# VM_Protection_Circuit.net
KiCad netlist of a schematic drawn in EAGLE
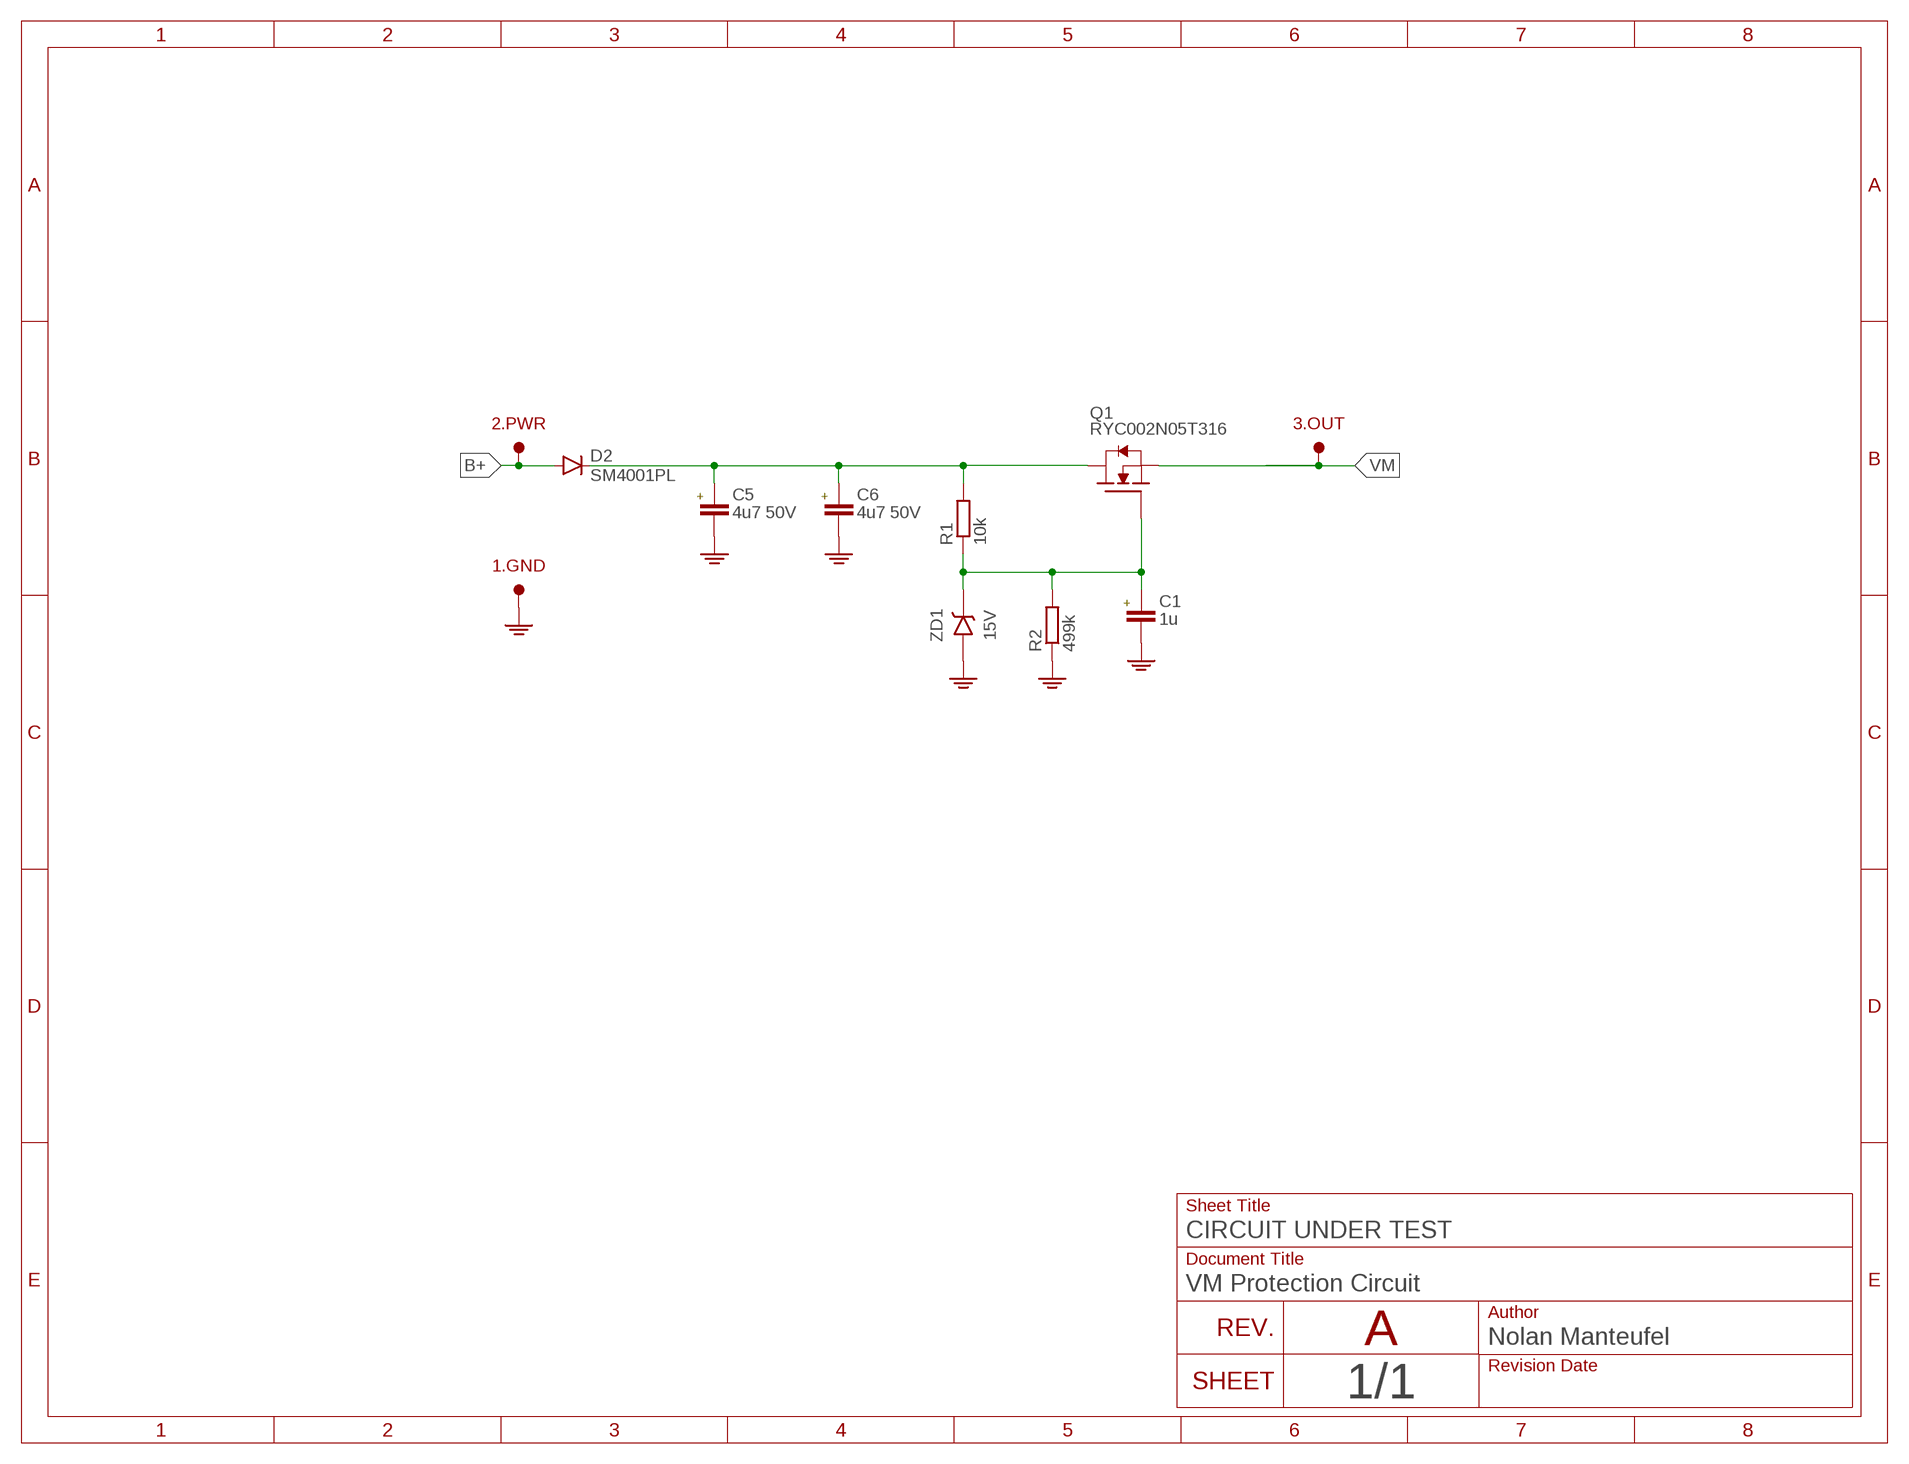
[diagram p0: schematic, sheet 1]

(export (version "E")
  (design (tool "Eeschema 10.0.6"))
  (components
    (comp (ref "1.GND")
      (value "TESTPOINTKE5000-SMTEXT")
      (footprint "eagle-import:PINS_1_TESTPOINT_KE5000_NOTEXT")
      (libsource (lib "eagle-import") (part "TESTPOINTKE5000-SMTEXT"))
    )
    (comp (ref "2.PWR")
      (value "TESTPOINTKE5000-SMTEXT")
      (footprint "eagle-import:PINS_1_TESTPOINT_KE5000_NOTEXT")
      (libsource (lib "eagle-import") (part "TESTPOINTKE5000-SMTEXT"))
    )
    (comp (ref "3.OUT")
      (value "TESTPOINTKE5000-SMTEXT")
      (footprint "eagle-import:PINS_1_TESTPOINT_KE5000_NOTEXT")
      (libsource (lib "eagle-import") (part "TESTPOINTKE5000-SMTEXT"))
    )
    (comp (ref "C1")
      (value "1u")
      (footprint "eagle-import:C0402")
      (libsource (lib "eagle-import") (part "C-EUC0402"))
    )
    (comp (ref "C5")
      (value "4u7 50V")
      (footprint "eagle-import:C0805")
      (libsource (lib "eagle-import") (part "C-EUC0805"))
    )
    (comp (ref "C6")
      (value "4u7 50V")
      (footprint "eagle-import:C0805")
      (libsource (lib "eagle-import") (part "C-EUC0805"))
    )
    (comp (ref "D2")
      (value "SM4001PL")
      (footprint "eagle-import:SOD123")
      (libsource (lib "eagle-import") (part "DIODE-SOD123"))
    )
    (comp (ref "Q1")
      (value "RYC002N05T316")
      (footprint "eagle-import:SOT23")
      (libsource (lib "eagle-import") (part "MOSFET-NSOT23"))
    )
    (comp (ref "R1")
      (value "10k")
      (footprint "eagle-import:R0402")
      (libsource (lib "eagle-import") (part "R-EU_R0402"))
    )
    (comp (ref "R2")
      (value "499k")
      (footprint "eagle-import:R0402")
      (libsource (lib "eagle-import") (part "R-EU_R0402"))
    )
    (comp (ref "ZD1")
      (value "15V")
      (footprint "eagle-import:SOT23")
      (libsource (lib "eagle-import") (part "ZENER-DIODESOT23"))
    )
  )
  (nets
    (net (code "1") (name "B+") (class "Default")
      (node (ref "2.PWR") (pin "1") (pinfunction "1_1") (pintype "bidirectional"))
      (node (ref "D2") (pin "A") (pinfunction "A_A") (pintype "passive"))
    )
    (net (code "2") (name "GND") (class "Default")
      (node (ref "1.GND") (pin "1") (pinfunction "1_1") (pintype "bidirectional"))
      (node (ref "C1") (pin "2") (pinfunction "2_2") (pintype "passive"))
      (node (ref "C5") (pin "2") (pinfunction "2_2") (pintype "passive"))
      (node (ref "C6") (pin "2") (pinfunction "2_2") (pintype "passive"))
      (node (ref "R2") (pin "1") (pinfunction "1_1") (pintype "passive"))
      (node (ref "ZD1") (pin "1") (pinfunction "A_1") (pintype "passive"))
    )
    (net (code "3") (name "Net-(Q1-D)") (class "Default")
      (node (ref "C5") (pin "1") (pinfunction "1_1") (pintype "passive"))
      (node (ref "C6") (pin "1") (pinfunction "1_1") (pintype "passive"))
      (node (ref "D2") (pin "C") (pinfunction "C_C") (pintype "passive"))
      (node (ref "Q1") (pin "3") (pinfunction "D_3") (pintype "passive"))
      (node (ref "R1") (pin "2") (pinfunction "2_2") (pintype "passive"))
    )
    (net (code "4") (name "Net-(Q1-G)") (class "Default")
      (node (ref "C1") (pin "1") (pinfunction "1_1") (pintype "passive"))
      (node (ref "Q1") (pin "1") (pinfunction "G_1") (pintype "passive"))
      (node (ref "R1") (pin "1") (pinfunction "1_1") (pintype "passive"))
      (node (ref "R2") (pin "2") (pinfunction "2_2") (pintype "passive"))
      (node (ref "ZD1") (pin "3") (pinfunction "C_3") (pintype "passive"))
    )
    (net (code "5") (name "VM") (class "Default")
      (node (ref "3.OUT") (pin "1") (pinfunction "1_1") (pintype "bidirectional"))
      (node (ref "Q1") (pin "2") (pinfunction "S_2") (pintype "passive"))
    )
  )
)
